# INPUT_OUTPUT.net
KiCad netlist of a schematic drawn in EAGLE
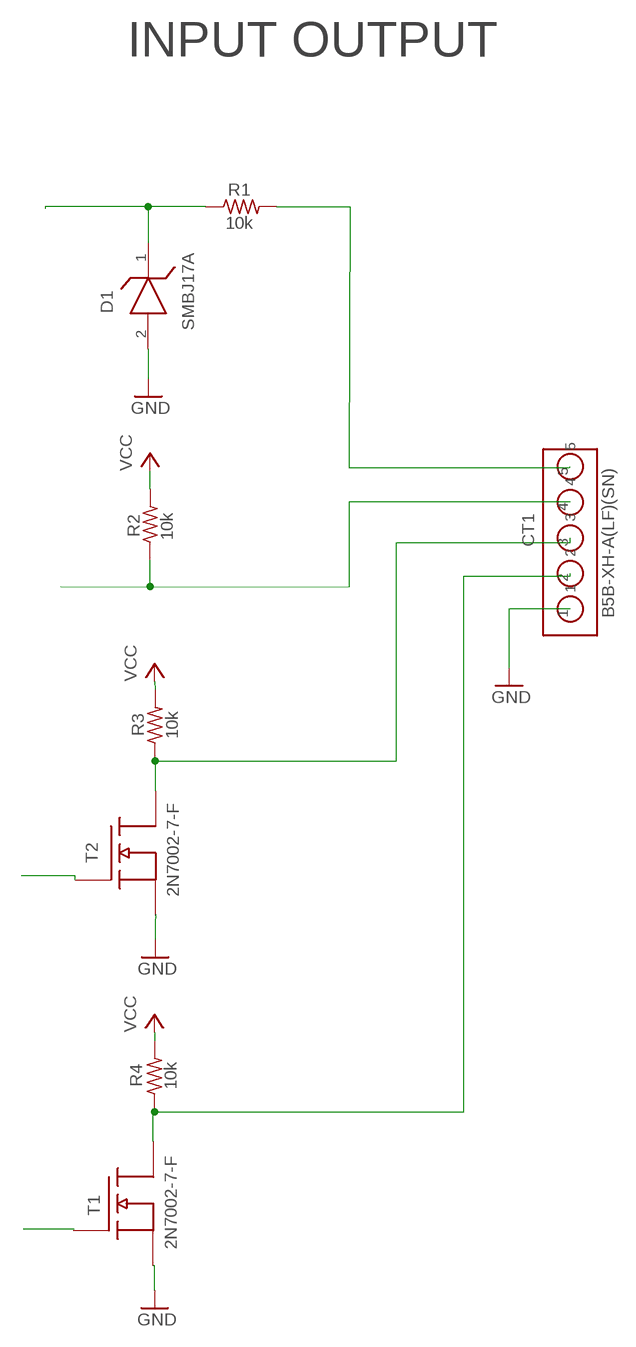
[diagram p0: schematic, sheet 1]

(export (version "E")
  (design (tool "Eeschema 10.0.6"))
  (components
    (comp (ref "CT1")
      (value "B5B-XH-A(LF)(SN)")
      (footprint "eagle-import:5-PIN-JST")
      (libsource (lib "eagle-import") (part "B5B-XH-A(LF)(SN)"))
    )
    (comp (ref "D1")
      (value "SMBJ17A")
      (footprint "eagle-import:DO-214AA")
      (libsource (lib "eagle-import") (part "SMBJ17A"))
    )
    (comp (ref "R1")
      (value "10k")
      (footprint "eagle-import:R0805")
      (fields (field (name "PARTNO") "Y40227K34000T9W"))
      (libsource (lib "eagle-import") (part "R-US_R0805"))
    )
    (comp (ref "R2")
      (value "10k")
      (footprint "eagle-import:R0805")
      (fields (field (name "PARTNO") "Y40227K34000T9W"))
      (libsource (lib "eagle-import") (part "R-US_R0805"))
    )
    (comp (ref "R3")
      (value "10k")
      (footprint "eagle-import:R0805")
      (fields (field (name "PARTNO") "Y40227K34000T9W"))
      (libsource (lib "eagle-import") (part "R-US_R0805"))
    )
    (comp (ref "R4")
      (value "10k")
      (footprint "eagle-import:R0805")
      (fields (field (name "PARTNO") "Y40227K34000T9W"))
      (libsource (lib "eagle-import") (part "R-US_R0805"))
    )
    (comp (ref "T1")
      (value "2N7002-7-F")
      (footprint "eagle-import:TO-236-3")
      (libsource (lib "eagle-import") (part "2N7002-7-F"))
    )
    (comp (ref "T2")
      (value "2N7002-7-F")
      (footprint "eagle-import:TO-236-3")
      (libsource (lib "eagle-import") (part "2N7002-7-F"))
    )
  )
  (nets
    (net (code "1") (name "GND") (class "Default")
      (node (ref "CT1") (pin "1") (pinfunction "1_1") (pintype "passive"))
      (node (ref "D1") (pin "2") (pinfunction "A_2") (pintype "passive"))
      (node (ref "T1") (pin "S") (pinfunction "SOURCE_S") (pintype "passive"))
    )
    (net (code "2") (name "Net-(CT1-Pad5)") (class "Default")
      (node (ref "CT1") (pin "5") (pinfunction "5_5") (pintype "passive"))
      (node (ref "R1") (pin "2") (pinfunction "2_2") (pintype "passive"))
    )
    (net (code "3") (name "Net-(D1-C)") (class "Default")
      (node (ref "D1") (pin "1") (pinfunction "C_1") (pintype "passive"))
      (node (ref "R1") (pin "1") (pinfunction "1_1") (pintype "passive"))
    )
    (net (code "4") (name "Net-(T1-DRAIN)") (class "Default")
      (node (ref "CT1") (pin "2") (pinfunction "2_2") (pintype "passive"))
      (node (ref "R4") (pin "1") (pinfunction "1_1") (pintype "passive"))
      (node (ref "T1") (pin "D") (pinfunction "DRAIN_D") (pintype "passive"))
    )
    (net (code "5") (name "Net-(T2-DRAIN)") (class "Default")
      (node (ref "CT1") (pin "3") (pinfunction "3_3") (pintype "passive"))
      (node (ref "R3") (pin "1") (pinfunction "1_1") (pintype "passive"))
      (node (ref "T2") (pin "D") (pinfunction "DRAIN_D") (pintype "passive"))
    )
    (net (code "6") (name "VCC") (class "Default")
      (node (ref "R2") (pin "2") (pinfunction "2_2") (pintype "passive"))
      (node (ref "R3") (pin "2") (pinfunction "2_2") (pintype "passive"))
      (node (ref "R4") (pin "2") (pinfunction "2_2") (pintype "passive"))
    )
    (net (code "7") (name "unconnected-(CT1-Pad4)") (class "Default")
      (node (ref "CT1") (pin "4") (pinfunction "4_4") (pintype "passive"))
    )
    (net (code "8") (name "unconnected-(R2-Pad1)") (class "Default")
      (node (ref "R2") (pin "1") (pinfunction "1_1") (pintype "passive"))
    )
    (net (code "9") (name "unconnected-(T1-GATE-PadG)") (class "Default")
      (node (ref "T1") (pin "G") (pinfunction "GATE_G") (pintype "passive"))
    )
    (net (code "10") (name "unconnected-(T2-GATE-PadG)") (class "Default")
      (node (ref "T2") (pin "G") (pinfunction "GATE_G") (pintype "passive"))
    )
    (net (code "11") (name "unconnected-(T2-SOURCE-PadS)") (class "Default")
      (node (ref "T2") (pin "S") (pinfunction "SOURCE_S") (pintype "passive"))
    )
  )
)
